# 06_GPIO.net
KiCad netlist of a schematic drawn in Altium Designer
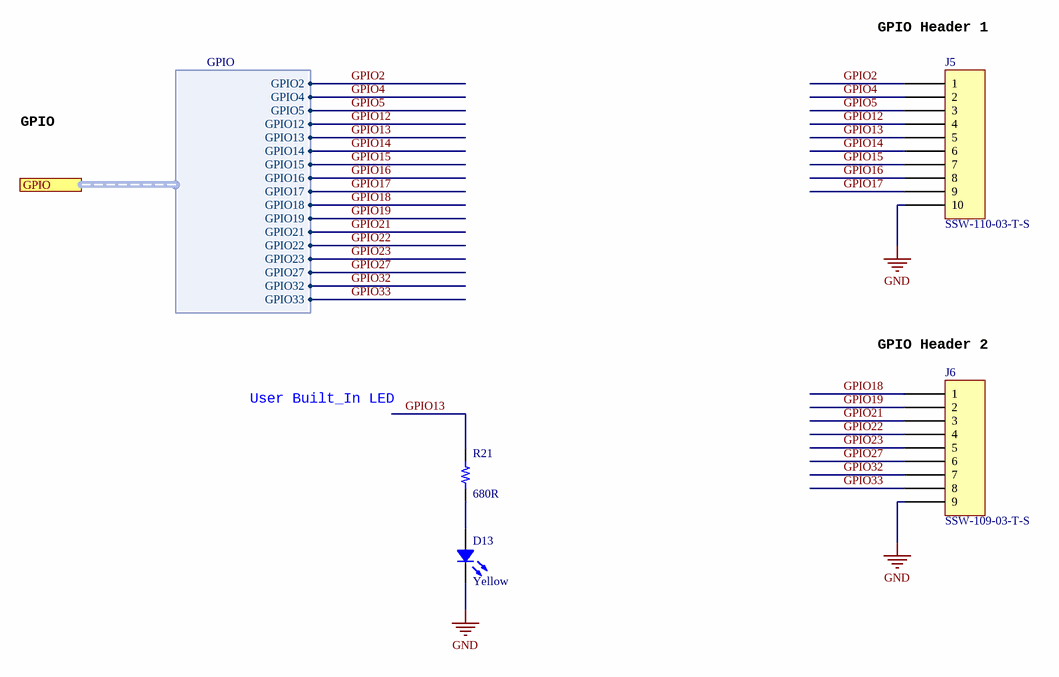
[diagram p0: 06.GPIO.SchDoc]

(export (version "E")
  (design (tool "Eeschema 10.0.6"))
  (components
    (comp (ref "D13")
      (value "Yellow")
      (footprint "LED 0603_1608 YELLOW")
      (description "无色透明透镜 -40℃~+85℃ 572nm Green-yellow 120° 60mW 0603 Light Emitting Diodes (LED) ROHS")
      (fields (field (name "MANUFACTURER PART NUMBER") "MHT192JGCT") (field (name "MANUFACTURER") "MEIHUA"))
      (libsource (lib "Celestial Altium Library - altium_library") (part "LED"))
    )
    (comp (ref "J5")
      (value "SSW-110-03-T-S")
      (footprint "SAMTEC SSW-110-03-T-S")
      (description "CONN RCPT 10POS 0.1 TIN PCB")
      (fields (field (name "MANUFACTURER") "Samtec Inc.") (field (name "JLC PART NUMBER") "C3322776"))
      (libsource (lib "Celestial Altium Library - altium_library") (part "10 Pin"))
    )
    (comp (ref "J6")
      (value "SSW-109-03-T-S")
      (footprint "SAMTEC SSW-109-03-T-S")
      (description "CONN RCPT 9POS 0.1 TIN PCB")
      (fields (field (name "MANUFACTURER") "Samtec Inc."))
      (libsource (lib "Celestial Altium Library - altium_library") (part "9 Pin"))
    )
    (comp (ref "R21")
      (value "680R")
      (footprint "RES 0603_1608")
      (description "100mW Thick Film Resistors ±100ppm/℃ ±1% 680Ω 0603 Chip Resistor - Surface Mount ROHS")
      (fields
        (field (name "MANUFACTURER PART NUMBER") "RC0603FR-07680RL")
        (field (name "MANUFACTURER") "YAGEO")
      )
      (libsource (lib "Celestial Altium Library - altium_library") (part "Resistor"))
    )
  )
  (nets
    (net (code "2") (name "/GPIO2") (class "Default")
      (node (ref "J5") (pin "1") (pinfunction "1_1") (pintype "passive"))
    )
    (net (code "3") (name "/GPIO4") (class "Default")
      (node (ref "J5") (pin "2") (pinfunction "2_2") (pintype "passive"))
    )
    (net (code "4") (name "/GPIO5") (class "Default")
      (node (ref "J5") (pin "3") (pinfunction "3_3") (pintype "passive"))
    )
    (net (code "5") (name "/GPIO12") (class "Default")
      (node (ref "J5") (pin "4") (pinfunction "4_4") (pintype "passive"))
    )
    (net (code "6") (name "/GPIO13") (class "Default")
      (node (ref "J5") (pin "5") (pinfunction "5_5") (pintype "passive"))
      (node (ref "R21") (pin "2") (pinfunction "2_2") (pintype "passive"))
    )
    (net (code "7") (name "/GPIO14") (class "Default")
      (node (ref "J5") (pin "6") (pinfunction "6_6") (pintype "passive"))
    )
    (net (code "8") (name "/GPIO15") (class "Default")
      (node (ref "J5") (pin "7") (pinfunction "7_7") (pintype "passive"))
    )
    (net (code "9") (name "/GPIO16") (class "Default")
      (node (ref "J5") (pin "8") (pinfunction "8_8") (pintype "passive"))
    )
    (net (code "10") (name "/GPIO17") (class "Default")
      (node (ref "J5") (pin "9") (pinfunction "9_9") (pintype "passive"))
    )
    (net (code "11") (name "/GPIO18") (class "Default")
      (node (ref "J6") (pin "1") (pinfunction "1_1") (pintype "passive"))
    )
    (net (code "12") (name "/GPIO19") (class "Default")
      (node (ref "J6") (pin "2") (pinfunction "2_2") (pintype "passive"))
    )
    (net (code "13") (name "/GPIO21") (class "Default")
      (node (ref "J6") (pin "3") (pinfunction "3_3") (pintype "passive"))
    )
    (net (code "14") (name "/GPIO22") (class "Default")
      (node (ref "J6") (pin "4") (pinfunction "4_4") (pintype "passive"))
    )
    (net (code "15") (name "/GPIO23") (class "Default")
      (node (ref "J6") (pin "5") (pinfunction "5_5") (pintype "passive"))
    )
    (net (code "16") (name "/GPIO27") (class "Default")
      (node (ref "J6") (pin "6") (pinfunction "6_6") (pintype "passive"))
    )
    (net (code "17") (name "/GPIO32") (class "Default")
      (node (ref "J6") (pin "7") (pinfunction "7_7") (pintype "passive"))
    )
    (net (code "18") (name "/GPIO33") (class "Default")
      (node (ref "J6") (pin "8") (pinfunction "8_8") (pintype "passive"))
    )
    (net (code "20") (name "GND") (class "Default")
      (node (ref "D13") (pin "2") (pinfunction "2_2") (pintype "passive"))
      (node (ref "J5") (pin "10") (pinfunction "10_10") (pintype "passive"))
      (node (ref "J6") (pin "9") (pinfunction "9_9") (pintype "passive"))
    )
    (net (code "21") (name "Net-(D13-Pad1)") (class "Default")
      (node (ref "D13") (pin "1") (pinfunction "1_1") (pintype "passive"))
      (node (ref "R21") (pin "1") (pinfunction "1_1") (pintype "passive"))
    )
  )
)
